# wifi-test.net
KiCad netlist of a schematic drawn in EAGLE
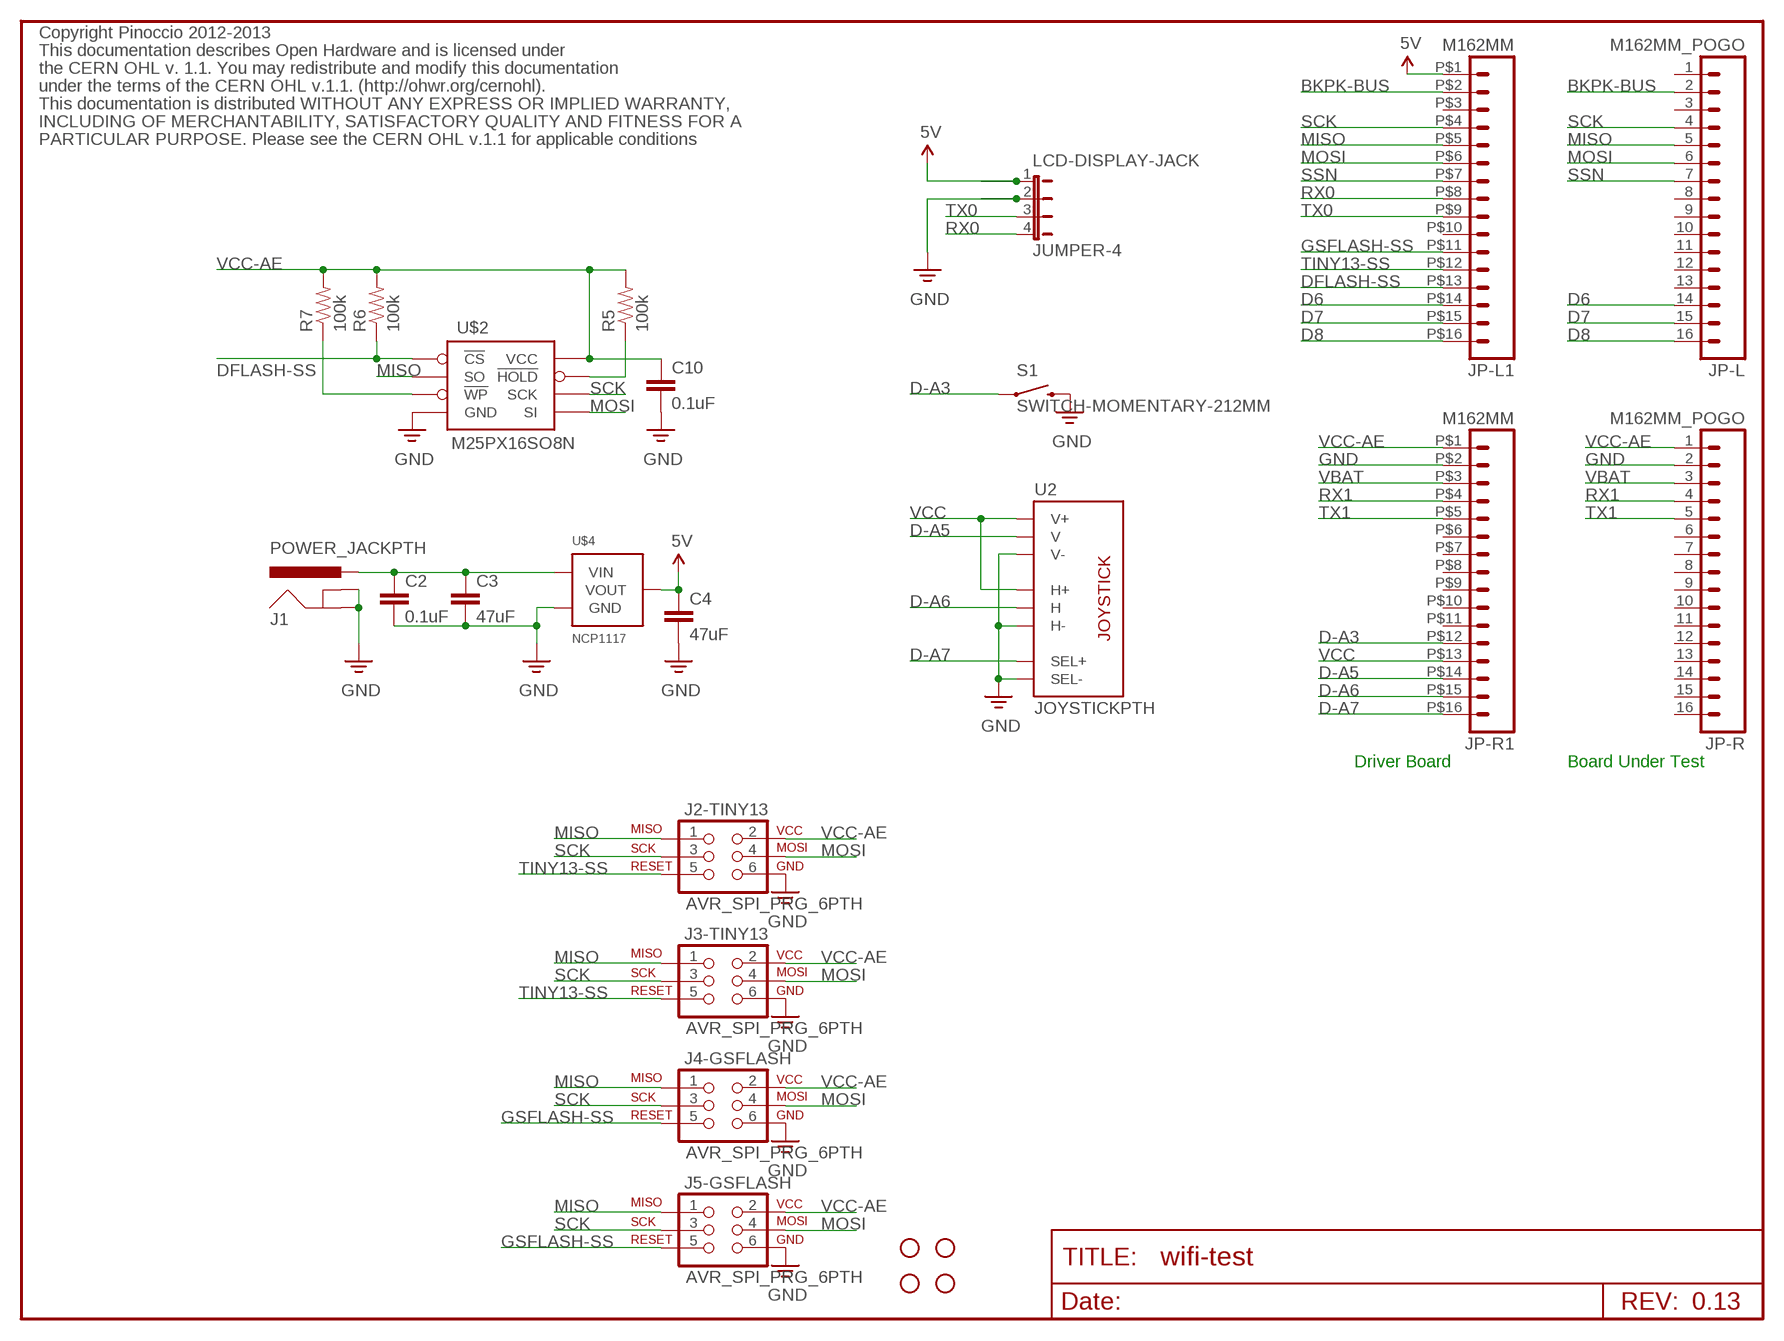
[diagram p0: schematic, sheet 1]

(export (version "E")
  (design (tool "Eeschema 10.0.6"))
  (components
    (comp (ref "C2")
      (value "0.1uF")
      (footprint "eagle-import:0402-CAP")
      (libsource (lib "eagle-import") (part "CAP0402-CAP"))
    )
    (comp (ref "C3")
      (value "47uF")
      (footprint "eagle-import:0805")
      (libsource (lib "eagle-import") (part "CAP0805"))
    )
    (comp (ref "C4")
      (value "47uF")
      (footprint "eagle-import:0805")
      (libsource (lib "eagle-import") (part "CAP0805"))
    )
    (comp (ref "C10")
      (value "0.1uF")
      (footprint "eagle-import:0402-CAP")
      (libsource (lib "eagle-import") (part "CAP0402-CAP"))
    )
    (comp (ref "J1")
      (value "POWER_JACKPTH")
      (footprint "eagle-import:POWER_JACK_PTH")
      (libsource (lib "eagle-import") (part "POWER_JACKPTH"))
    )
    (comp (ref "J2-TINY13")
      (value "AVR_SPI_PRG_6PTH")
      (footprint "eagle-import:2X3")
      (libsource (lib "eagle-import") (part "AVR_SPI_PRG_6PTH"))
    )
    (comp (ref "J3-TINY13")
      (value "AVR_SPI_PRG_6PTH")
      (footprint "eagle-import:2X3")
      (libsource (lib "eagle-import") (part "AVR_SPI_PRG_6PTH"))
    )
    (comp (ref "J4-GSFLASH")
      (value "AVR_SPI_PRG_6PTH")
      (footprint "eagle-import:2X3")
      (libsource (lib "eagle-import") (part "AVR_SPI_PRG_6PTH"))
    )
    (comp (ref "J5-GSFLASH")
      (value "AVR_SPI_PRG_6PTH")
      (footprint "eagle-import:2X3")
      (libsource (lib "eagle-import") (part "AVR_SPI_PRG_6PTH"))
    )
    (comp (ref "JP-L")
      (value "M162MM_POGO")
      (footprint "eagle-import:1X16_2MM_POGO")
      (libsource (lib "eagle-import") (part "M162MM_POGO"))
    )
    (comp (ref "JP-L1")
      (value "M162MM")
      (footprint "eagle-import:1X16_2MM")
      (libsource (lib "eagle-import") (part "M162MM"))
    )
    (comp (ref "JP-R")
      (value "M162MM_POGO")
      (footprint "eagle-import:1X16_2MM_POGO")
      (libsource (lib "eagle-import") (part "M162MM_POGO"))
    )
    (comp (ref "JP-R1")
      (value "M162MM")
      (footprint "eagle-import:1X16_2MM")
      (libsource (lib "eagle-import") (part "M162MM"))
    )
    (comp (ref "JP7")
      (value "STAND-OFF")
      (footprint "eagle-import:STAND-OFF")
      (libsource (lib "eagle-import") (part "STAND-OFF"))
    )
    (comp (ref "JP9")
      (value "STAND-OFF")
      (footprint "eagle-import:STAND-OFF")
      (libsource (lib "eagle-import") (part "STAND-OFF"))
    )
    (comp (ref "JP10")
      (value "STAND-OFF")
      (footprint "eagle-import:STAND-OFF")
      (libsource (lib "eagle-import") (part "STAND-OFF"))
    )
    (comp (ref "JP12")
      (value "STAND-OFF")
      (footprint "eagle-import:STAND-OFF")
      (libsource (lib "eagle-import") (part "STAND-OFF"))
    )
    (comp (ref "LCD-DISPLAY-JACK")
      (value "JUMPER-4")
      (footprint "eagle-import:1X04")
      (libsource (lib "eagle-import") (part "JUMPER-4"))
    )
    (comp (ref "R5")
      (value "100k")
      (footprint "eagle-import:0402-RES")
      (libsource (lib "eagle-import") (part "RESISTOR0402-RES"))
    )
    (comp (ref "R6")
      (value "100k")
      (footprint "eagle-import:0402-RES")
      (libsource (lib "eagle-import") (part "RESISTOR0402-RES"))
    )
    (comp (ref "R7")
      (value "100k")
      (footprint "eagle-import:0402-RES")
      (libsource (lib "eagle-import") (part "RESISTOR0402-RES"))
    )
    (comp (ref "S1")
      (value "SWITCH-MOMENTARY-212MM")
      (footprint "eagle-import:TACTILE-PTH-12MM")
      (libsource (lib "eagle-import") (part "SWITCH-MOMENTARY-212MM"))
    )
    (comp (ref "U$2")
      (value "M25PX16SO8N")
      (footprint "eagle-import:SO8N")
      (libsource (lib "eagle-import") (part "M25PX16SO8N"))
    )
    (comp (ref "U$4")
      (value "NCP1117")
      (footprint "eagle-import:SOT223")
      (libsource (lib "eagle-import") (part "NCP1117"))
    )
    (comp (ref "U2")
      (value "JOYSTICKPTH")
      (footprint "eagle-import:JOYSTICK")
      (libsource (lib "eagle-import") (part "JOYSTICKPTH"))
    )
  )
  (nets
    (net (code "1") (name "/BKPK-BUS") (class "Default")
      (node (ref "JP-L") (pin "2") (pinfunction "2_2") (pintype "passive"))
      (node (ref "JP-L1") (pin "P$2") (pinfunction "2_P$2") (pintype "passive"))
    )
    (net (code "2") (name "/D-A3") (class "Default")
      (node (ref "JP-R1") (pin "P$12") (pinfunction "12_P$12") (pintype "passive"))
      (node (ref "S1") (pin "1") (pinfunction "1_1") (pintype "passive"))
    )
    (net (code "3") (name "/D-A5") (class "Default")
      (node (ref "JP-R1") (pin "P$14") (pinfunction "14_P$14") (pintype "passive"))
      (node (ref "U2") (pin "V2") (pinfunction "V_V2") (pintype "bidirectional"))
    )
    (net (code "4") (name "/D-A6") (class "Default")
      (node (ref "JP-R1") (pin "P$15") (pinfunction "15_P$15") (pintype "passive"))
      (node (ref "U2") (pin "H2") (pinfunction "H_H2") (pintype "bidirectional"))
    )
    (net (code "5") (name "/D-A7") (class "Default")
      (node (ref "JP-R1") (pin "P$16") (pinfunction "16_P$16") (pintype "passive"))
      (node (ref "U2") (pin "B1A") (pinfunction "SEL+_B1A") (pintype "bidirectional"))
    )
    (net (code "6") (name "/D6") (class "Default")
      (node (ref "JP-L") (pin "14") (pinfunction "14_14") (pintype "passive"))
      (node (ref "JP-L1") (pin "P$14") (pinfunction "14_P$14") (pintype "passive"))
    )
    (net (code "7") (name "/D7") (class "Default")
      (node (ref "JP-L") (pin "15") (pinfunction "15_15") (pintype "passive"))
      (node (ref "JP-L1") (pin "P$15") (pinfunction "15_P$15") (pintype "passive"))
    )
    (net (code "8") (name "/D8") (class "Default")
      (node (ref "JP-L") (pin "16") (pinfunction "16_16") (pintype "passive"))
      (node (ref "JP-L1") (pin "P$16") (pinfunction "16_P$16") (pintype "passive"))
    )
    (net (code "9") (name "/DFLASH-SS") (class "Default")
      (node (ref "JP-L1") (pin "P$13") (pinfunction "13_P$13") (pintype "passive"))
      (node (ref "R6") (pin "1") (pinfunction "1_1") (pintype "passive"))
      (node (ref "U$2") (pin "1") (pinfunction "~{CS}_1") (pintype "bidirectional"))
    )
    (net (code "10") (name "/GSFLASH-SS") (class "Default")
      (node (ref "J4-GSFLASH") (pin "5") (pinfunction "5_5") (pintype "passive"))
      (node (ref "J5-GSFLASH") (pin "5") (pinfunction "5_5") (pintype "passive"))
      (node (ref "JP-L1") (pin "P$11") (pinfunction "11_P$11") (pintype "passive"))
    )
    (net (code "11") (name "/MISO") (class "Default")
      (node (ref "J2-TINY13") (pin "1") (pinfunction "1_1") (pintype "passive"))
      (node (ref "J3-TINY13") (pin "1") (pinfunction "1_1") (pintype "passive"))
      (node (ref "J4-GSFLASH") (pin "1") (pinfunction "1_1") (pintype "passive"))
      (node (ref "J5-GSFLASH") (pin "1") (pinfunction "1_1") (pintype "passive"))
      (node (ref "JP-L") (pin "5") (pinfunction "5_5") (pintype "passive"))
      (node (ref "JP-L1") (pin "P$5") (pinfunction "5_P$5") (pintype "passive"))
      (node (ref "U$2") (pin "2") (pinfunction "SO_2") (pintype "bidirectional"))
    )
    (net (code "12") (name "/MOSI") (class "Default")
      (node (ref "J2-TINY13") (pin "4") (pinfunction "4_4") (pintype "passive"))
      (node (ref "J3-TINY13") (pin "4") (pinfunction "4_4") (pintype "passive"))
      (node (ref "J4-GSFLASH") (pin "4") (pinfunction "4_4") (pintype "passive"))
      (node (ref "J5-GSFLASH") (pin "4") (pinfunction "4_4") (pintype "passive"))
      (node (ref "JP-L") (pin "6") (pinfunction "6_6") (pintype "passive"))
      (node (ref "JP-L1") (pin "P$6") (pinfunction "6_P$6") (pintype "passive"))
      (node (ref "U$2") (pin "5") (pinfunction "SI_5") (pintype "bidirectional"))
    )
    (net (code "13") (name "/RX0") (class "Default")
      (node (ref "JP-L1") (pin "P$8") (pinfunction "8_P$8") (pintype "passive"))
      (node (ref "LCD-DISPLAY-JACK") (pin "4") (pinfunction "4_4") (pintype "passive"))
    )
    (net (code "14") (name "/RX1") (class "Default")
      (node (ref "JP-R") (pin "4") (pinfunction "4_4") (pintype "passive"))
      (node (ref "JP-R1") (pin "P$4") (pinfunction "4_P$4") (pintype "passive"))
    )
    (net (code "15") (name "/SCK") (class "Default")
      (node (ref "J2-TINY13") (pin "3") (pinfunction "3_3") (pintype "passive"))
      (node (ref "J3-TINY13") (pin "3") (pinfunction "3_3") (pintype "passive"))
      (node (ref "J4-GSFLASH") (pin "3") (pinfunction "3_3") (pintype "passive"))
      (node (ref "J5-GSFLASH") (pin "3") (pinfunction "3_3") (pintype "passive"))
      (node (ref "JP-L") (pin "4") (pinfunction "4_4") (pintype "passive"))
      (node (ref "JP-L1") (pin "P$4") (pinfunction "4_P$4") (pintype "passive"))
      (node (ref "U$2") (pin "6") (pinfunction "SCK_6") (pintype "bidirectional"))
    )
    (net (code "16") (name "/SSN") (class "Default")
      (node (ref "JP-L") (pin "7") (pinfunction "7_7") (pintype "passive"))
      (node (ref "JP-L1") (pin "P$7") (pinfunction "7_P$7") (pintype "passive"))
    )
    (net (code "17") (name "/TINY13-SS") (class "Default")
      (node (ref "J2-TINY13") (pin "5") (pinfunction "5_5") (pintype "passive"))
      (node (ref "J3-TINY13") (pin "5") (pinfunction "5_5") (pintype "passive"))
      (node (ref "JP-L1") (pin "P$12") (pinfunction "12_P$12") (pintype "passive"))
    )
    (net (code "18") (name "/TX0") (class "Default")
      (node (ref "JP-L1") (pin "P$9") (pinfunction "9_P$9") (pintype "passive"))
      (node (ref "LCD-DISPLAY-JACK") (pin "3") (pinfunction "3_3") (pintype "passive"))
    )
    (net (code "19") (name "/TX1") (class "Default")
      (node (ref "JP-R") (pin "5") (pinfunction "5_5") (pintype "passive"))
      (node (ref "JP-R1") (pin "P$5") (pinfunction "5_P$5") (pintype "passive"))
    )
    (net (code "20") (name "/VBAT") (class "Default")
      (node (ref "JP-R") (pin "3") (pinfunction "3_3") (pintype "passive"))
      (node (ref "JP-R1") (pin "P$3") (pinfunction "3_P$3") (pintype "passive"))
    )
    (net (code "21") (name "/VCC") (class "Default")
      (node (ref "JP-R1") (pin "P$13") (pinfunction "13_P$13") (pintype "passive"))
      (node (ref "U2") (pin "H1") (pinfunction "H+_H1") (pintype "bidirectional"))
      (node (ref "U2") (pin "V1") (pinfunction "V+_V1") (pintype "bidirectional"))
    )
    (net (code "22") (name "/VCC-AE") (class "Default")
      (node (ref "C10") (pin "1") (pinfunction "1_1") (pintype "passive"))
      (node (ref "J2-TINY13") (pin "2") (pinfunction "2_2") (pintype "passive"))
      (node (ref "J3-TINY13") (pin "2") (pinfunction "2_2") (pintype "passive"))
      (node (ref "J4-GSFLASH") (pin "2") (pinfunction "2_2") (pintype "passive"))
      (node (ref "J5-GSFLASH") (pin "2") (pinfunction "2_2") (pintype "passive"))
      (node (ref "JP-R") (pin "1") (pinfunction "1_1") (pintype "passive"))
      (node (ref "JP-R1") (pin "P$1") (pinfunction "1_P$1") (pintype "passive"))
      (node (ref "R5") (pin "2") (pinfunction "2_2") (pintype "passive"))
      (node (ref "R6") (pin "2") (pinfunction "2_2") (pintype "passive"))
      (node (ref "R7") (pin "2") (pinfunction "2_2") (pintype "passive"))
      (node (ref "U$2") (pin "8") (pinfunction "VCC_8") (pintype "bidirectional"))
    )
    (net (code "23") (name "5V") (class "Default")
      (node (ref "C4") (pin "1") (pinfunction "1_1") (pintype "passive"))
      (node (ref "JP-L1") (pin "P$1") (pinfunction "1_P$1") (pintype "passive"))
      (node (ref "LCD-DISPLAY-JACK") (pin "1") (pinfunction "1_1") (pintype "passive"))
      (node (ref "U$4") (pin "2") (pinfunction "VOUT_2") (pintype "bidirectional"))
      (node (ref "U$4") (pin "4") (pinfunction "VOUT_4") (pintype "bidirectional"))
    )
    (net (code "24") (name "GND") (class "Default")
      (node (ref "C10") (pin "2") (pinfunction "2_2") (pintype "passive"))
      (node (ref "C2") (pin "2") (pinfunction "2_2") (pintype "passive"))
      (node (ref "C3") (pin "2") (pinfunction "2_2") (pintype "passive"))
      (node (ref "C4") (pin "2") (pinfunction "2_2") (pintype "passive"))
      (node (ref "J1") (pin "GND") (pinfunction "GND_GND") (pintype "bidirectional"))
      (node (ref "J1") (pin "GNDBREAK") (pinfunction "GNDBREAK_GNDBREAK") (pintype "bidirectional"))
      (node (ref "J2-TINY13") (pin "6") (pinfunction "6_6") (pintype "passive"))
      (node (ref "J3-TINY13") (pin "6") (pinfunction "6_6") (pintype "passive"))
      (node (ref "J4-GSFLASH") (pin "6") (pinfunction "6_6") (pintype "passive"))
      (node (ref "J5-GSFLASH") (pin "6") (pinfunction "6_6") (pintype "passive"))
      (node (ref "JP-R") (pin "2") (pinfunction "2_2") (pintype "passive"))
      (node (ref "JP-R1") (pin "P$2") (pinfunction "2_P$2") (pintype "passive"))
      (node (ref "LCD-DISPLAY-JACK") (pin "2") (pinfunction "2_2") (pintype "passive"))
      (node (ref "S1") (pin "3") (pinfunction "2_3") (pintype "passive"))
      (node (ref "U$2") (pin "4") (pinfunction "GND_4") (pintype "bidirectional"))
      (node (ref "U$4") (pin "1") (pinfunction "GND_1") (pintype "bidirectional"))
      (node (ref "U2") (pin "B2A") (pinfunction "SEL-_B2A") (pintype "bidirectional"))
      (node (ref "U2") (pin "H3") (pinfunction "H-_H3") (pintype "bidirectional"))
      (node (ref "U2") (pin "V3") (pinfunction "V-_V3") (pintype "bidirectional"))
    )
    (net (code "25") (name "Net-(U$2-~{HOLD})") (class "Default")
      (node (ref "R5") (pin "1") (pinfunction "1_1") (pintype "passive"))
      (node (ref "U$2") (pin "7") (pinfunction "~{HOLD}_7") (pintype "bidirectional"))
    )
    (net (code "26") (name "Net-(U$2-~{WP})") (class "Default")
      (node (ref "R7") (pin "1") (pinfunction "1_1") (pintype "passive"))
      (node (ref "U$2") (pin "3") (pinfunction "~{WP}_3") (pintype "bidirectional"))
    )
    (net (code "27") (name "Net-(U$4-VIN)") (class "Default")
      (node (ref "C2") (pin "1") (pinfunction "1_1") (pintype "passive"))
      (node (ref "C3") (pin "1") (pinfunction "1_1") (pintype "passive"))
      (node (ref "J1") (pin "PWR") (pinfunction "PWR_PWR") (pintype "bidirectional"))
      (node (ref "U$4") (pin "3") (pinfunction "VIN_3") (pintype "bidirectional"))
    )
    (net (code "28") (name "unconnected-(JP-L-Pad1)") (class "Default")
      (node (ref "JP-L") (pin "1") (pinfunction "1_1") (pintype "passive"))
    )
    (net (code "29") (name "unconnected-(JP-L-Pad3)") (class "Default")
      (node (ref "JP-L") (pin "3") (pinfunction "3_3") (pintype "passive"))
    )
    (net (code "30") (name "unconnected-(JP-L-Pad8)") (class "Default")
      (node (ref "JP-L") (pin "8") (pinfunction "8_8") (pintype "passive"))
    )
    (net (code "31") (name "unconnected-(JP-L-Pad9)") (class "Default")
      (node (ref "JP-L") (pin "9") (pinfunction "9_9") (pintype "passive"))
    )
    (net (code "32") (name "unconnected-(JP-L-Pad10)") (class "Default")
      (node (ref "JP-L") (pin "10") (pinfunction "10_10") (pintype "passive"))
    )
    (net (code "33") (name "unconnected-(JP-L-Pad11)") (class "Default")
      (node (ref "JP-L") (pin "11") (pinfunction "11_11") (pintype "passive"))
    )
    (net (code "34") (name "unconnected-(JP-L-Pad12)") (class "Default")
      (node (ref "JP-L") (pin "12") (pinfunction "12_12") (pintype "passive"))
    )
    (net (code "35") (name "unconnected-(JP-L-Pad13)") (class "Default")
      (node (ref "JP-L") (pin "13") (pinfunction "13_13") (pintype "passive"))
    )
    (net (code "36") (name "unconnected-(JP-L1-3-PadP$3)") (class "Default")
      (node (ref "JP-L1") (pin "P$3") (pinfunction "3_P$3") (pintype "passive"))
    )
    (net (code "37") (name "unconnected-(JP-L1-10-PadP$10)") (class "Default")
      (node (ref "JP-L1") (pin "P$10") (pinfunction "10_P$10") (pintype "passive"))
    )
    (net (code "38") (name "unconnected-(JP-R-Pad6)") (class "Default")
      (node (ref "JP-R") (pin "6") (pinfunction "6_6") (pintype "passive"))
    )
    (net (code "39") (name "unconnected-(JP-R-Pad7)") (class "Default")
      (node (ref "JP-R") (pin "7") (pinfunction "7_7") (pintype "passive"))
    )
    (net (code "40") (name "unconnected-(JP-R-Pad8)") (class "Default")
      (node (ref "JP-R") (pin "8") (pinfunction "8_8") (pintype "passive"))
    )
    (net (code "41") (name "unconnected-(JP-R-Pad9)") (class "Default")
      (node (ref "JP-R") (pin "9") (pinfunction "9_9") (pintype "passive"))
    )
    (net (code "42") (name "unconnected-(JP-R-Pad10)") (class "Default")
      (node (ref "JP-R") (pin "10") (pinfunction "10_10") (pintype "passive"))
    )
    (net (code "43") (name "unconnected-(JP-R-Pad11)") (class "Default")
      (node (ref "JP-R") (pin "11") (pinfunction "11_11") (pintype "passive"))
    )
    (net (code "44") (name "unconnected-(JP-R-Pad12)") (class "Default")
      (node (ref "JP-R") (pin "12") (pinfunction "12_12") (pintype "passive"))
    )
    (net (code "45") (name "unconnected-(JP-R-Pad13)") (class "Default")
      (node (ref "JP-R") (pin "13") (pinfunction "13_13") (pintype "passive"))
    )
    (net (code "46") (name "unconnected-(JP-R-Pad14)") (class "Default")
      (node (ref "JP-R") (pin "14") (pinfunction "14_14") (pintype "passive"))
    )
    (net (code "47") (name "unconnected-(JP-R-Pad15)") (class "Default")
      (node (ref "JP-R") (pin "15") (pinfunction "15_15") (pintype "passive"))
    )
    (net (code "48") (name "unconnected-(JP-R-Pad16)") (class "Default")
      (node (ref "JP-R") (pin "16") (pinfunction "16_16") (pintype "passive"))
    )
    (net (code "49") (name "unconnected-(JP-R1-6-PadP$6)") (class "Default")
      (node (ref "JP-R1") (pin "P$6") (pinfunction "6_P$6") (pintype "passive"))
    )
    (net (code "50") (name "unconnected-(JP-R1-7-PadP$7)") (class "Default")
      (node (ref "JP-R1") (pin "P$7") (pinfunction "7_P$7") (pintype "passive"))
    )
    (net (code "51") (name "unconnected-(JP-R1-8-PadP$8)") (class "Default")
      (node (ref "JP-R1") (pin "P$8") (pinfunction "8_P$8") (pintype "passive"))
    )
    (net (code "52") (name "unconnected-(JP-R1-9-PadP$9)") (class "Default")
      (node (ref "JP-R1") (pin "P$9") (pinfunction "9_P$9") (pintype "passive"))
    )
    (net (code "53") (name "unconnected-(JP-R1-10-PadP$10)") (class "Default")
      (node (ref "JP-R1") (pin "P$10") (pinfunction "10_P$10") (pintype "passive"))
    )
    (net (code "54") (name "unconnected-(JP-R1-11-PadP$11)") (class "Default")
      (node (ref "JP-R1") (pin "P$11") (pinfunction "11_P$11") (pintype "passive"))
    )
  )
)
